# 4_LED_strip.net
KiCad netlist of a schematic drawn in Altium Designer
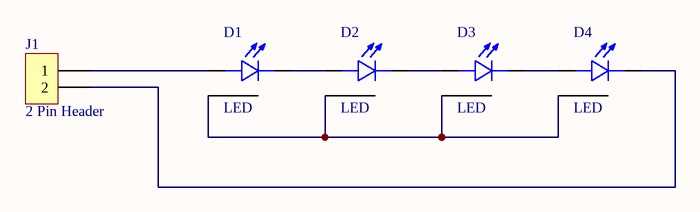
[diagram p0: 4_LED_strip.SchDoc]

(export (version "E")
  (design (tool "Eeschema 10.0.6"))
  (components
    (comp (ref "D1")
      (value "LED")
      (footprint "LED_SMD_CREE_3.45x3.45")
      (libsource (lib "Schlib") (part "LED"))
    )
    (comp (ref "D2")
      (value "LED")
      (footprint "LED_SMD_CREE_3.45x3.45")
      (libsource (lib "Schlib") (part "LED"))
    )
    (comp (ref "D3")
      (value "LED")
      (footprint "LED_SMD_CREE_3.45x3.45")
      (libsource (lib "Schlib") (part "LED"))
    )
    (comp (ref "D4")
      (value "LED")
      (footprint "LED_SMD_CREE_3.45x3.45")
      (libsource (lib "Schlib") (part "LED"))
    )
    (comp (ref "J1")
      (value "2 Pin Header")
      (footprint "2POS_SMD_2.5mm_CON")
      (libsource (lib "Schlib") (part "2 Pin Header"))
    )
  )
  (nets
    (net (code "1") (name "Net-(D1-PadA)") (class "Default")
      (node (ref "D1") (pin "A") (pinfunction "A_A") (pintype "passive"))
      (node (ref "J1") (pin "1") (pinfunction "1_1") (pintype "passive"))
    )
    (net (code "2") (name "Net-(D1-PadC)") (class "Default")
      (node (ref "D1") (pin "C") (pinfunction "C_C") (pintype "passive"))
      (node (ref "D2") (pin "A") (pinfunction "A_A") (pintype "passive"))
    )
    (net (code "3") (name "Net-(D1-TH_PAD)") (class "Default")
      (node (ref "D1") (pin "3") (pinfunction "TH_PAD_3") (pintype "passive"))
      (node (ref "D2") (pin "3") (pinfunction "TH_PAD_3") (pintype "passive"))
      (node (ref "D3") (pin "3") (pinfunction "TH_PAD_3") (pintype "passive"))
      (node (ref "D4") (pin "3") (pinfunction "TH_PAD_3") (pintype "passive"))
    )
    (net (code "4") (name "Net-(D2-PadC)") (class "Default")
      (node (ref "D2") (pin "C") (pinfunction "C_C") (pintype "passive"))
      (node (ref "D3") (pin "A") (pinfunction "A_A") (pintype "passive"))
    )
    (net (code "5") (name "Net-(D3-PadC)") (class "Default")
      (node (ref "D3") (pin "C") (pinfunction "C_C") (pintype "passive"))
      (node (ref "D4") (pin "A") (pinfunction "A_A") (pintype "passive"))
    )
    (net (code "6") (name "Net-(D4-PadC)") (class "Default")
      (node (ref "D4") (pin "C") (pinfunction "C_C") (pintype "passive"))
      (node (ref "J1") (pin "2") (pinfunction "2_2") (pintype "passive"))
    )
  )
)
